# PAGE3_-_POWER.net
KiCad netlist of a schematic drawn in Altium Designer
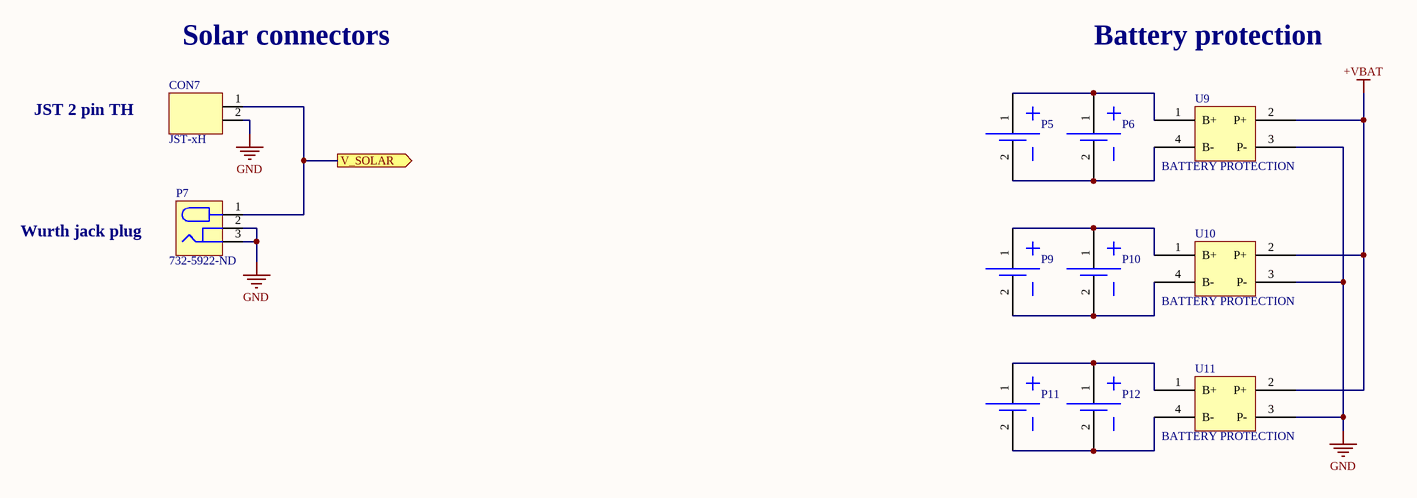
[diagram p0: PAGE3 - POWER.SchDoc]

(export (version "E")
  (design (tool "Eeschema 10.0.6"))
  (components
    (comp (ref "CON7")
      (value "JST-xH")
      (footprint "JST_2PIN_TH")
      (description "Wire-To-Board Connector, Vertical, 2.5 mm, 2 Contacts, Header, XH Series, Through Hole, 1 Rows")
      (libsource (lib "Connectors") (part "B2B-XH-A (LF)(SN)"))
    )
    (comp (ref "P5")
      (value "BAT - 18650")
      (footprint "BATTERY HOLDER 18650")
      (description "BATERRY HOLDER 18650")
      (libsource (lib "Mechanical") (part "BAT - 18650"))
    )
    (comp (ref "P6")
      (value "BAT - 18650")
      (footprint "BATTERY HOLDER 18650")
      (description "BATERRY HOLDER 18650")
      (libsource (lib "Mechanical") (part "BAT - 18650"))
    )
    (comp (ref "P7")
      (value "732-5922-ND")
      (footprint "732-5922-ND")
      (description "Power Barrel Connector Jack 1.05mm ID (0.041\"), 3.50mm OD (0.138\") Through Hole, Right Angle")
      (libsource (lib "Connectors") (part "CONN PWR JACK 1.05X3.5MM"))
    )
    (comp (ref "P9")
      (value "BAT - 18650")
      (footprint "BATTERY HOLDER 18650")
      (description "BATERRY HOLDER 18650")
      (libsource (lib "Mechanical") (part "BAT - 18650"))
    )
    (comp (ref "P10")
      (value "BAT - 18650")
      (footprint "BATTERY HOLDER 18650")
      (description "BATERRY HOLDER 18650")
      (libsource (lib "Mechanical") (part "BAT - 18650"))
    )
    (comp (ref "P11")
      (value "BAT - 18650")
      (footprint "BATTERY HOLDER 18650")
      (description "BATERRY HOLDER 18650")
      (libsource (lib "Mechanical") (part "BAT - 18650"))
    )
    (comp (ref "P12")
      (value "BAT - 18650")
      (footprint "BATTERY HOLDER 18650")
      (description "BATERRY HOLDER 18650")
      (libsource (lib "Mechanical") (part "BAT - 18650"))
    )
    (comp (ref "U9")
      (value "BATTERY PROTECTION")
      (footprint "BATTERY PROTECTION")
      (libsource (lib "Mechanical") (part "BATTERY PROTECTION"))
    )
    (comp (ref "U10")
      (value "BATTERY PROTECTION")
      (footprint "BATTERY PROTECTION")
      (libsource (lib "Mechanical") (part "BATTERY PROTECTION"))
    )
    (comp (ref "U11")
      (value "BATTERY PROTECTION")
      (footprint "BATTERY PROTECTION")
      (libsource (lib "Mechanical") (part "BATTERY PROTECTION"))
    )
  )
  (nets
    (net (code "1") (name "+VBAT") (class "Default")
      (node (ref "U10") (pin "2") (pinfunction "P+_2") (pintype "passive"))
      (node (ref "U11") (pin "2") (pinfunction "P+_2") (pintype "passive"))
      (node (ref "U9") (pin "2") (pinfunction "P+_2") (pintype "passive"))
    )
    (net (code "2") (name "/V_SOLAR") (class "Default")
      (node (ref "CON7") (pin "1") (pinfunction "1_1") (pintype "passive"))
      (node (ref "P7") (pin "1") (pinfunction "1_1") (pintype "passive"))
    )
    (net (code "3") (name "GND") (class "Default")
      (node (ref "CON7") (pin "2") (pinfunction "2_2") (pintype "passive"))
      (node (ref "P7") (pin "2") (pinfunction "2_2") (pintype "passive"))
      (node (ref "P7") (pin "3") (pinfunction "3_3") (pintype "passive"))
      (node (ref "U10") (pin "3") (pinfunction "P-_3") (pintype "passive"))
      (node (ref "U11") (pin "3") (pinfunction "P-_3") (pintype "passive"))
      (node (ref "U9") (pin "3") (pinfunction "P-_3") (pintype "passive"))
    )
    (net (code "4") (name "Net-(U9-B+)") (class "Default")
      (node (ref "P5") (pin "1") (pintype "passive"))
      (node (ref "P6") (pin "1") (pintype "passive"))
      (node (ref "U9") (pin "1") (pinfunction "B+_1") (pintype "passive"))
    )
    (net (code "5") (name "Net-(U9-B-)") (class "Default")
      (node (ref "P5") (pin "2") (pintype "passive"))
      (node (ref "P6") (pin "2") (pintype "passive"))
      (node (ref "U9") (pin "4") (pinfunction "B-_4") (pintype "passive"))
    )
    (net (code "6") (name "Net-(U10-B+)") (class "Default")
      (node (ref "P10") (pin "1") (pintype "passive"))
      (node (ref "P9") (pin "1") (pintype "passive"))
      (node (ref "U10") (pin "1") (pinfunction "B+_1") (pintype "passive"))
    )
    (net (code "7") (name "Net-(U10-B-)") (class "Default")
      (node (ref "P10") (pin "2") (pintype "passive"))
      (node (ref "P9") (pin "2") (pintype "passive"))
      (node (ref "U10") (pin "4") (pinfunction "B-_4") (pintype "passive"))
    )
    (net (code "8") (name "Net-(U11-B+)") (class "Default")
      (node (ref "P11") (pin "1") (pintype "passive"))
      (node (ref "P12") (pin "1") (pintype "passive"))
      (node (ref "U11") (pin "1") (pinfunction "B+_1") (pintype "passive"))
    )
    (net (code "9") (name "Net-(U11-B-)") (class "Default")
      (node (ref "P11") (pin "2") (pintype "passive"))
      (node (ref "P12") (pin "2") (pintype "passive"))
      (node (ref "U11") (pin "4") (pinfunction "B-_4") (pintype "passive"))
    )
  )
)
